# Sheet2_nRF52840_module.net
KiCad netlist of a schematic drawn in Altium Designer
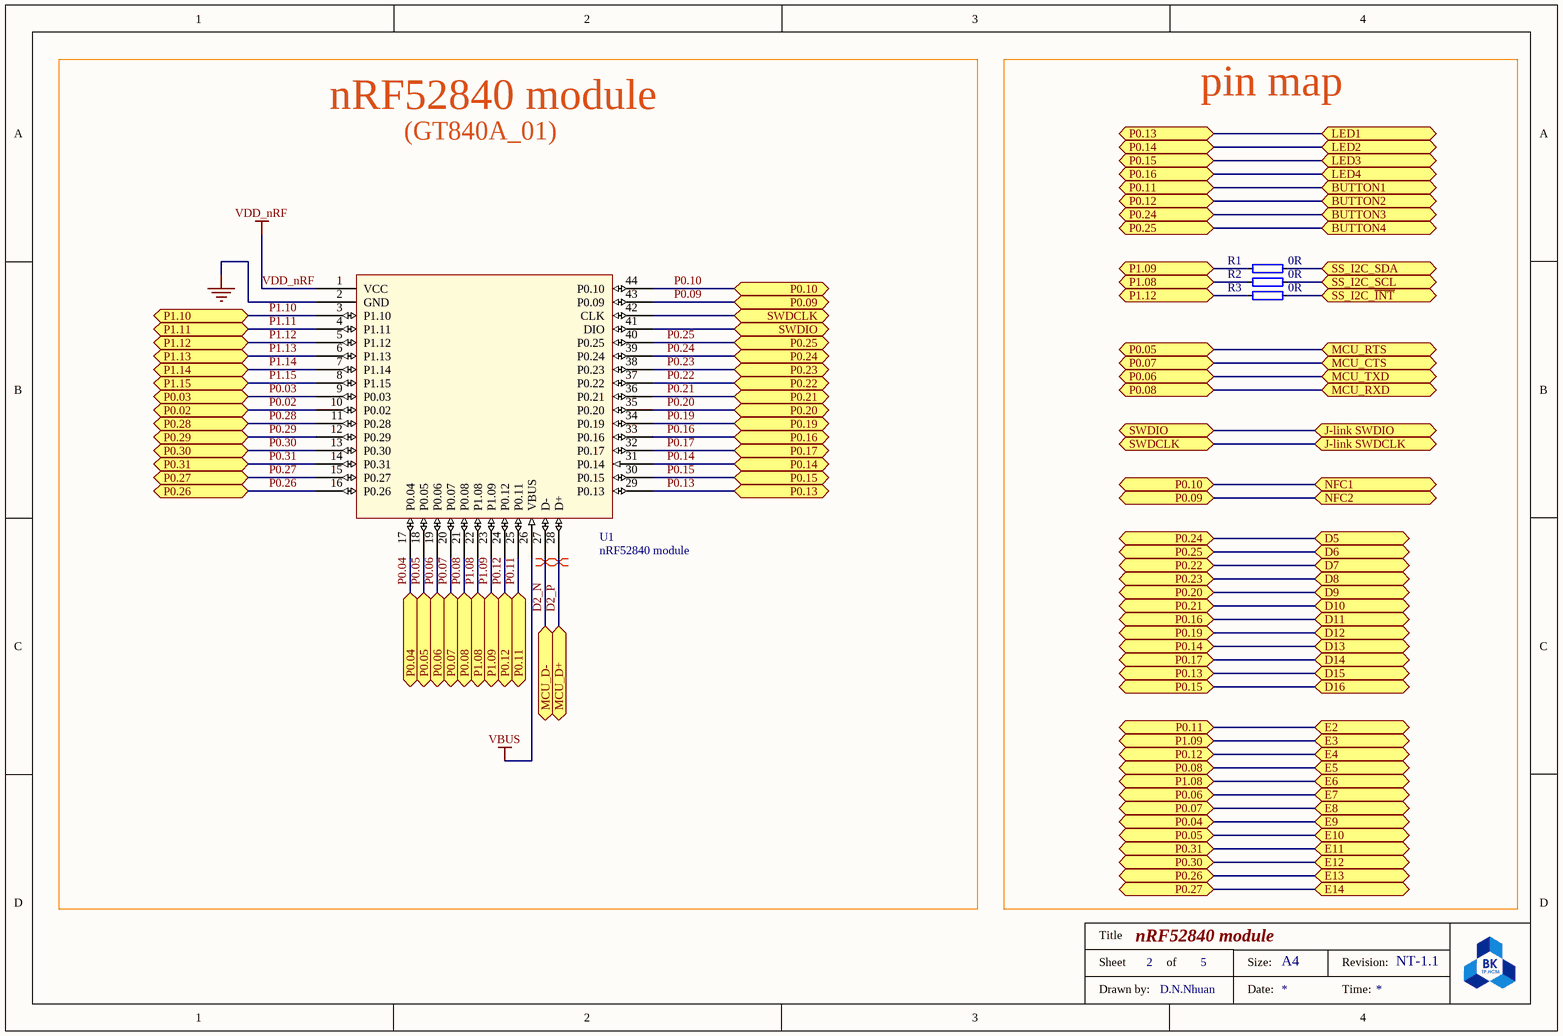
[diagram p0: Sheet2_nRF52840_module.SchDoc]

(export (version "E")
  (design (tool "Eeschema 10.0.6"))
  (components
    (comp (ref "R1")
      (value "0R")
      (footprint "0402 imperial")
      (description "General Schematic")
      (fields (field (name "TOLERANCE") "±5%"))
      (libsource (lib "Project_Library") (part "Resistor"))
    )
    (comp (ref "R2")
      (value "0R")
      (footprint "0402 imperial")
      (description "General Schematic")
      (fields (field (name "TOLERANCE") "±5%"))
      (libsource (lib "Project_Library") (part "Resistor"))
    )
    (comp (ref "R3")
      (value "0R")
      (footprint "0402 imperial")
      (description "General Schematic")
      (fields (field (name "TOLERANCE") "±5%"))
      (libsource (lib "Project_Library") (part "Resistor"))
    )
    (comp (ref "U1")
      (value "nRF52840 module")
      (footprint "nRF52840_GT840A01")
      (description "nRF52840 module GT840A_01")
      (libsource (lib "Project_Library") (part "nRF52840_GT840A01"))
    )
  )
  (nets
    (net (code "1") (name "/D2_N") (class "Default")
      (node (ref "U1") (pin "27") (pinfunction "D-_27") (pintype "bidirectional"))
    )
    (net (code "2") (name "/D2_P") (class "Default")
      (node (ref "U1") (pin "28") (pinfunction "D+_28") (pintype "bidirectional"))
    )
    (net (code "3") (name "/J-link SWDCLK") (class "Default")
      (node (ref "U1") (pin "42") (pinfunction "CLK_42") (pintype "bidirectional"))
    )
    (net (code "4") (name "/J-link SWDIO") (class "Default")
      (node (ref "U1") (pin "41") (pinfunction "DIO_41") (pintype "bidirectional"))
    )
    (net (code "5") (name "/P0.02") (class "Default")
      (node (ref "U1") (pin "10") (pinfunction "P0.02_10") (pintype "bidirectional"))
    )
    (net (code "6") (name "/P0.03") (class "Default")
      (node (ref "U1") (pin "9") (pinfunction "P0.03_9") (pintype "bidirectional"))
    )
    (net (code "7") (name "/P0.04") (class "Default")
      (node (ref "U1") (pin "17") (pinfunction "P0.04_17") (pintype "bidirectional"))
    )
    (net (code "8") (name "/P0.05") (class "Default")
      (node (ref "U1") (pin "18") (pinfunction "P0.05_18") (pintype "bidirectional"))
    )
    (net (code "9") (name "/P0.06") (class "Default")
      (node (ref "U1") (pin "19") (pinfunction "P0.06_19") (pintype "bidirectional"))
    )
    (net (code "10") (name "/P0.07") (class "Default")
      (node (ref "U1") (pin "20") (pinfunction "P0.07_20") (pintype "bidirectional"))
    )
    (net (code "11") (name "/P0.08") (class "Default")
      (node (ref "U1") (pin "21") (pinfunction "P0.08_21") (pintype "bidirectional"))
    )
    (net (code "12") (name "/P0.09") (class "Default")
      (node (ref "U1") (pin "43") (pinfunction "P0.09_43") (pintype "bidirectional"))
    )
    (net (code "13") (name "/P0.10") (class "Default")
      (node (ref "U1") (pin "44") (pinfunction "P0.10_44") (pintype "bidirectional"))
    )
    (net (code "14") (name "/P0.11") (class "Default")
      (node (ref "U1") (pin "25") (pinfunction "P0.11_25") (pintype "bidirectional"))
    )
    (net (code "15") (name "/P0.12") (class "Default")
      (node (ref "U1") (pin "24") (pinfunction "P0.12_24") (pintype "bidirectional"))
    )
    (net (code "16") (name "/P0.13") (class "Default")
      (node (ref "U1") (pin "29") (pinfunction "P0.13_29") (pintype "bidirectional"))
    )
    (net (code "17") (name "/P0.14") (class "Default")
      (node (ref "U1") (pin "31") (pinfunction "P0.14_31") (pintype "input"))
    )
    (net (code "18") (name "/P0.15") (class "Default")
      (node (ref "U1") (pin "30") (pinfunction "P0.15_30") (pintype "bidirectional"))
    )
    (net (code "19") (name "/P0.16") (class "Default")
      (node (ref "U1") (pin "33") (pinfunction "P0.16_33") (pintype "bidirectional"))
    )
    (net (code "20") (name "/P0.17") (class "Default")
      (node (ref "U1") (pin "32") (pinfunction "P0.17_32") (pintype "bidirectional"))
    )
    (net (code "21") (name "/P0.19") (class "Default")
      (node (ref "U1") (pin "34") (pinfunction "P0.19_34") (pintype "bidirectional"))
    )
    (net (code "22") (name "/P0.20") (class "Default")
      (node (ref "U1") (pin "35") (pinfunction "P0.20_35") (pintype "bidirectional"))
    )
    (net (code "23") (name "/P0.21") (class "Default")
      (node (ref "U1") (pin "36") (pinfunction "P0.21_36") (pintype "bidirectional"))
    )
    (net (code "24") (name "/P0.22") (class "Default")
      (node (ref "U1") (pin "37") (pinfunction "P0.22_37") (pintype "bidirectional"))
    )
    (net (code "25") (name "/P0.23") (class "Default")
      (node (ref "U1") (pin "38") (pinfunction "P0.23_38") (pintype "bidirectional"))
    )
    (net (code "26") (name "/P0.24") (class "Default")
      (node (ref "U1") (pin "39") (pinfunction "P0.24_39") (pintype "bidirectional"))
    )
    (net (code "27") (name "/P0.25") (class "Default")
      (node (ref "U1") (pin "40") (pinfunction "P0.25_40") (pintype "bidirectional"))
    )
    (net (code "28") (name "/P0.26") (class "Default")
      (node (ref "U1") (pin "16") (pinfunction "P0.26_16") (pintype "bidirectional"))
    )
    (net (code "29") (name "/P0.27") (class "Default")
      (node (ref "U1") (pin "15") (pinfunction "P0.27_15") (pintype "bidirectional"))
    )
    (net (code "30") (name "/P0.28") (class "Default")
      (node (ref "U1") (pin "11") (pinfunction "P0.28_11") (pintype "bidirectional"))
    )
    (net (code "31") (name "/P0.29") (class "Default")
      (node (ref "U1") (pin "12") (pinfunction "P0.29_12") (pintype "bidirectional"))
    )
    (net (code "32") (name "/P0.30") (class "Default")
      (node (ref "U1") (pin "13") (pinfunction "P0.30_13") (pintype "bidirectional"))
    )
    (net (code "33") (name "/P0.31") (class "Default")
      (node (ref "U1") (pin "14") (pinfunction "P0.31_14") (pintype "bidirectional"))
    )
    (net (code "34") (name "/P1.08") (class "Default")
      (node (ref "R2") (pin "1") (pinfunction "1_1") (pintype "passive"))
      (node (ref "U1") (pin "22") (pinfunction "P1.08_22") (pintype "bidirectional"))
    )
    (net (code "35") (name "/P1.09") (class "Default")
      (node (ref "R1") (pin "1") (pinfunction "1_1") (pintype "passive"))
      (node (ref "U1") (pin "23") (pinfunction "P1.09_23") (pintype "bidirectional"))
    )
    (net (code "36") (name "/P1.10") (class "Default")
      (node (ref "U1") (pin "3") (pinfunction "P1.10_3") (pintype "bidirectional"))
    )
    (net (code "37") (name "/P1.11") (class "Default")
      (node (ref "U1") (pin "4") (pinfunction "P1.11_4") (pintype "bidirectional"))
    )
    (net (code "38") (name "/P1.12") (class "Default")
      (node (ref "R3") (pin "1") (pinfunction "1_1") (pintype "passive"))
      (node (ref "U1") (pin "5") (pinfunction "P1.12_5") (pintype "bidirectional"))
    )
    (net (code "39") (name "/P1.13") (class "Default")
      (node (ref "U1") (pin "6") (pinfunction "P1.13_6") (pintype "bidirectional"))
    )
    (net (code "40") (name "/P1.14") (class "Default")
      (node (ref "U1") (pin "7") (pinfunction "P1.14_7") (pintype "bidirectional"))
    )
    (net (code "41") (name "/P1.15") (class "Default")
      (node (ref "U1") (pin "8") (pinfunction "P1.15_8") (pintype "bidirectional"))
    )
    (net (code "42") (name "/SS_I2C_SCL") (class "Default")
      (node (ref "R2") (pin "2") (pinfunction "2_2") (pintype "passive"))
    )
    (net (code "43") (name "/SS_I2C_SDA") (class "Default")
      (node (ref "R1") (pin "2") (pinfunction "2_2") (pintype "passive"))
    )
    (net (code "44") (name "/SS_I2C_~{INT}") (class "Default")
      (node (ref "R3") (pin "2") (pinfunction "2_2") (pintype "passive"))
    )
    (net (code "45") (name "GND") (class "Default")
      (node (ref "U1") (pin "2") (pinfunction "GND_2") (pintype "power_in"))
    )
    (net (code "46") (name "VBUS") (class "Default")
      (node (ref "U1") (pin "26") (pinfunction "VBUS_26") (pintype "input"))
    )
    (net (code "47") (name "VDD_nRF") (class "Default")
      (node (ref "U1") (pin "1") (pinfunction "VCC_1") (pintype "power_in"))
    )
  )
)
